# PowerPath.net
KiCad netlist of a schematic drawn in Altium Designer
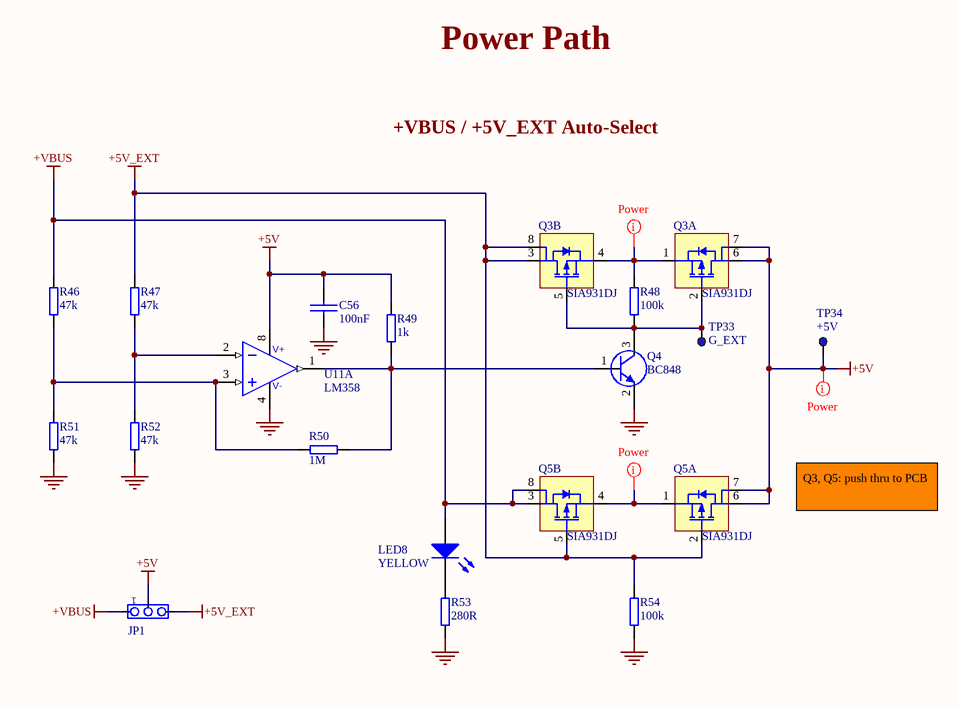
[diagram p0: PowerPath.SchDoc]

(export (version "E")
  (design (tool "Eeschema 10.0.6"))
  (components
    (comp (ref "C56")
      (value "100nF")
      (footprint "C0603")
      (description "CAP CER 0.1UF 50V X7R 0603")
      (fields (field (name "PART NUMBER") "C0603C104K5RACTU") (field (name "MANUFACTURER") "Kemet"))
      (libsource (lib "AKLib") (part "CAP"))
    )
    (comp (ref "JP1")
      (value "JP")
      (footprint "HDR1x3")
      (description "CONN HEADER 3 POS 2.54")
      (fields
        (field (name "PART NUMBER") "61300311121")
        (field (name "MANUFACTURER") "Wurth Electronics Inc.")
      )
      (libsource (lib "AKLib") (part "JP1x3"))
    )
    (comp (ref "LED8")
      (value "YELLOW")
      (footprint "LED_0603_YELLOW")
      (description "LED YELLOW CLEAR 0603 SMD")
      (fields (field (name "PART NUMBER") "LTST-C190KSKT") (field (name "MANUFACTURER") "Lite-On Inc."))
      (libsource (lib "AKLib") (part "LED"))
    )
    (comp (ref "Q3")
      (value "SIA931DJ")
      (footprint "PowerPAK SC-70-6L Dual")
      (description "MOSFET 2P-CH 30V 4.5A SC70-6L")
      (fields (field (name "PART NUMBER") "SIA931DJ-T1-GE3") (field (name "MANUFACTURER") "Vishay Siliconix"))
      (libsource (lib "AKLib") (part "SiA931DJ"))
    )
    (comp (ref "Q4")
      (value "BC848")
      (footprint "SC-70")
      (description "TRANS NPN 30V 0.1A SOT323")
      (fields (field (name "PART NUMBER") "BC848W,115") (field (name "MANUFACTURER") "Nexperia USA Inc."))
      (libsource (lib "AKLib") (part "NPN"))
    )
    (comp (ref "Q5")
      (value "SIA931DJ")
      (footprint "PowerPAK SC-70-6L Dual")
      (description "MOSFET 2P-CH 30V 4.5A SC70-6L")
      (fields (field (name "PART NUMBER") "SIA931DJ-T1-GE3") (field (name "MANUFACTURER") "Vishay Siliconix"))
      (libsource (lib "AKLib") (part "SiA931DJ"))
    )
    (comp (ref "R46")
      (value "47k")
      (footprint "R0603")
      (description "RES SMD 47K OHM 1% 1/10W 0603")
      (fields (field (name "PART NUMBER") "RC0603FR-0747KL") (field (name "MANUFACTURER") "Yageo"))
      (libsource (lib "AKLib") (part "RES"))
    )
    (comp (ref "R47")
      (value "47k")
      (footprint "R0603")
      (description "RES SMD 47K OHM 1% 1/10W 0603")
      (fields (field (name "PART NUMBER") "RC0603FR-0747KL") (field (name "MANUFACTURER") "Yageo"))
      (libsource (lib "AKLib") (part "RES"))
    )
    (comp (ref "R48")
      (value "100k")
      (footprint "R0603")
      (description "RES SMD 100K OHM 1% 1/10W 0603")
      (fields (field (name "PART NUMBER") "RC0603FR-07100KL") (field (name "MANUFACTURER") "Yageo"))
      (libsource (lib "AKLib") (part "RES"))
    )
    (comp (ref "R49")
      (value "1k")
      (footprint "R0603")
      (description "RES SMD 1K OHM 1% 1/10W 0603")
      (fields (field (name "PART NUMBER") "CRCW06031K00FKEA") (field (name "MANUFACTURER") "Vishay Dale"))
      (libsource (lib "AKLib") (part "RES"))
    )
    (comp (ref "R50")
      (value "1M")
      (footprint "R0603")
      (description "RES SMD 1M OHM 1% 1/10W 0603")
      (fields (field (name "PART NUMBER") "RC0603FR-071ML") (field (name "MANUFACTURER") "Yageo"))
      (libsource (lib "AKLib") (part "RES"))
    )
    (comp (ref "R51")
      (value "47k")
      (footprint "R0603")
      (description "RES SMD 47K OHM 1% 1/10W 0603")
      (fields (field (name "PART NUMBER") "RC0603FR-0747KL") (field (name "MANUFACTURER") "Yageo"))
      (libsource (lib "AKLib") (part "RES"))
    )
    (comp (ref "R52")
      (value "47k")
      (footprint "R0603")
      (description "RES SMD 47K OHM 1% 1/10W 0603")
      (fields (field (name "PART NUMBER") "RC0603FR-0747KL") (field (name "MANUFACTURER") "Yageo"))
      (libsource (lib "AKLib") (part "RES"))
    )
    (comp (ref "R53")
      (value "280R")
      (footprint "R0603")
      (description "RES SMD 280 OHM 1% 1/10W 0603")
      (fields (field (name "PART NUMBER") "RC0603FR-07280RL") (field (name "MANUFACTURER") "Yageo"))
      (libsource (lib "AKLib") (part "RES"))
    )
    (comp (ref "R54")
      (value "100k")
      (footprint "R0603")
      (description "RES SMD 100K OHM 1% 1/10W 0603")
      (fields (field (name "PART NUMBER") "RC0603FR-07100KL") (field (name "MANUFACTURER") "Yageo"))
      (libsource (lib "AKLib") (part "RES"))
    )
    (comp (ref "TP33")
      (value "G_EXT")
      (footprint "TP_1mm")
      (fields (field (name "PART NUMBER") "TP"))
      (libsource (lib "AKLib") (part "TP"))
    )
    (comp (ref "TP34")
      (value "+5V")
      (footprint "TP_1mm")
      (fields (field (name "PART NUMBER") "TP"))
      (libsource (lib "AKLib") (part "TP"))
    )
    (comp (ref "U11")
      (value "LM358")
      (footprint "DFN 2x2_LM358")
      (description "IC OPAMP GP 1.1MHZ 8DFN")
      (fields (field (name "PART NUMBER") "LM358QT") (field (name "MANUFACTURER") "STMicroelectronics"))
      (libsource (lib "AKLib") (part "LM358"))
    )
  )
  (nets
    (net (code "1") (name "+5V") (class "Default")
      (node (ref "C56") (pin "2") (pinfunction "2_2") (pintype "passive"))
      (node (ref "JP1") (pin "2") (pinfunction "2_2") (pintype "passive"))
      (node (ref "Q3") (pin "6") (pinfunction "D1_6") (pintype "passive"))
      (node (ref "Q3") (pin "7") (pinfunction "D1_7") (pintype "passive"))
      (node (ref "Q5") (pin "6") (pinfunction "D1_6") (pintype "passive"))
      (node (ref "Q5") (pin "7") (pinfunction "D1_7") (pintype "passive"))
      (node (ref "R49") (pin "2") (pinfunction "2_2") (pintype "passive"))
      (node (ref "TP34") (pin "1") (pinfunction "1_1") (pintype "passive"))
      (node (ref "U11") (pin "8") (pinfunction "V+_8") (pintype "power_in"))
    )
    (net (code "2") (name "+5V_EXT") (class "Default")
      (node (ref "JP1") (pin "3") (pinfunction "3_3") (pintype "passive"))
      (node (ref "Q3") (pin "3") (pinfunction "D2_3") (pintype "passive"))
      (node (ref "Q3") (pin "8") (pinfunction "D2_8") (pintype "passive"))
      (node (ref "Q5") (pin "2") (pinfunction "G1_2") (pintype "passive"))
      (node (ref "Q5") (pin "5") (pinfunction "G2_5") (pintype "passive"))
      (node (ref "R47") (pin "2") (pinfunction "2_2") (pintype "passive"))
      (node (ref "R54") (pin "2") (pinfunction "2_2") (pintype "passive"))
    )
    (net (code "3") (name "+VBUS") (class "Default")
      (node (ref "JP1") (pin "1") (pinfunction "1_1") (pintype "passive"))
      (node (ref "LED8") (pin "1") (pinfunction "A_1") (pintype "passive"))
      (node (ref "Q5") (pin "3") (pinfunction "D2_3") (pintype "passive"))
      (node (ref "Q5") (pin "8") (pinfunction "D2_8") (pintype "passive"))
      (node (ref "R46") (pin "2") (pinfunction "2_2") (pintype "passive"))
    )
    (net (code "4") (name "GND") (class "Default")
      (node (ref "C56") (pin "1") (pinfunction "1_1") (pintype "passive"))
      (node (ref "Q4") (pin "2") (pinfunction "2_2") (pintype "passive"))
      (node (ref "R51") (pin "1") (pinfunction "1_1") (pintype "passive"))
      (node (ref "R52") (pin "1") (pinfunction "1_1") (pintype "passive"))
      (node (ref "R53") (pin "1") (pinfunction "1_1") (pintype "passive"))
      (node (ref "R54") (pin "1") (pinfunction "1_1") (pintype "passive"))
      (node (ref "U11") (pin "4") (pinfunction "V-_4") (pintype "power_in"))
    )
    (net (code "5") (name "Net-(LED8-K)") (class "Default")
      (node (ref "LED8") (pin "2") (pinfunction "K_2") (pintype "passive"))
      (node (ref "R53") (pin "2") (pinfunction "2_2") (pintype "passive"))
    )
    (net (code "6") (name "Net-(Q3A-G1)") (class "Default")
      (node (ref "Q3") (pin "2") (pinfunction "G1_2") (pintype "passive"))
      (node (ref "Q3") (pin "5") (pinfunction "G2_5") (pintype "passive"))
      (node (ref "Q4") (pin "3") (pinfunction "3_3") (pintype "passive"))
      (node (ref "R48") (pin "1") (pinfunction "1_1") (pintype "passive"))
      (node (ref "TP33") (pin "1") (pinfunction "1_1") (pintype "passive"))
    )
    (net (code "7") (name "Net-(Q3A-S1)") (class "Default")
      (node (ref "Q3") (pin "1") (pinfunction "S1_1") (pintype "passive"))
      (node (ref "Q3") (pin "4") (pinfunction "S2_4") (pintype "passive"))
      (node (ref "R48") (pin "2") (pinfunction "2_2") (pintype "passive"))
    )
    (net (code "8") (name "Net-(Q5A-S1)") (class "Default")
      (node (ref "Q5") (pin "1") (pinfunction "S1_1") (pintype "passive"))
      (node (ref "Q5") (pin "4") (pinfunction "S2_4") (pintype "passive"))
    )
    (net (code "9") (name "Net-(U11A-IN+)") (class "Default")
      (node (ref "R46") (pin "1") (pinfunction "1_1") (pintype "passive"))
      (node (ref "R50") (pin "2") (pinfunction "2_2") (pintype "passive"))
      (node (ref "R51") (pin "2") (pinfunction "2_2") (pintype "passive"))
      (node (ref "U11") (pin "3") (pinfunction "IN+_3") (pintype "input"))
    )
    (net (code "10") (name "Net-(U11A-IN-)") (class "Default")
      (node (ref "R47") (pin "1") (pinfunction "1_1") (pintype "passive"))
      (node (ref "R52") (pin "2") (pinfunction "2_2") (pintype "passive"))
      (node (ref "U11") (pin "2") (pinfunction "IN-_2") (pintype "input"))
    )
    (net (code "11") (name "Net-(U11A-OUT)") (class "Default")
      (node (ref "Q4") (pin "1") (pinfunction "1_1") (pintype "passive"))
      (node (ref "R49") (pin "1") (pinfunction "1_1") (pintype "passive"))
      (node (ref "R50") (pin "1") (pinfunction "1_1") (pintype "passive"))
      (node (ref "U11") (pin "1") (pinfunction "OUT_1") (pintype "output"))
    )
  )
)
